# weaver_multisw.net
KiCad netlist of a schematic drawn in EAGLE
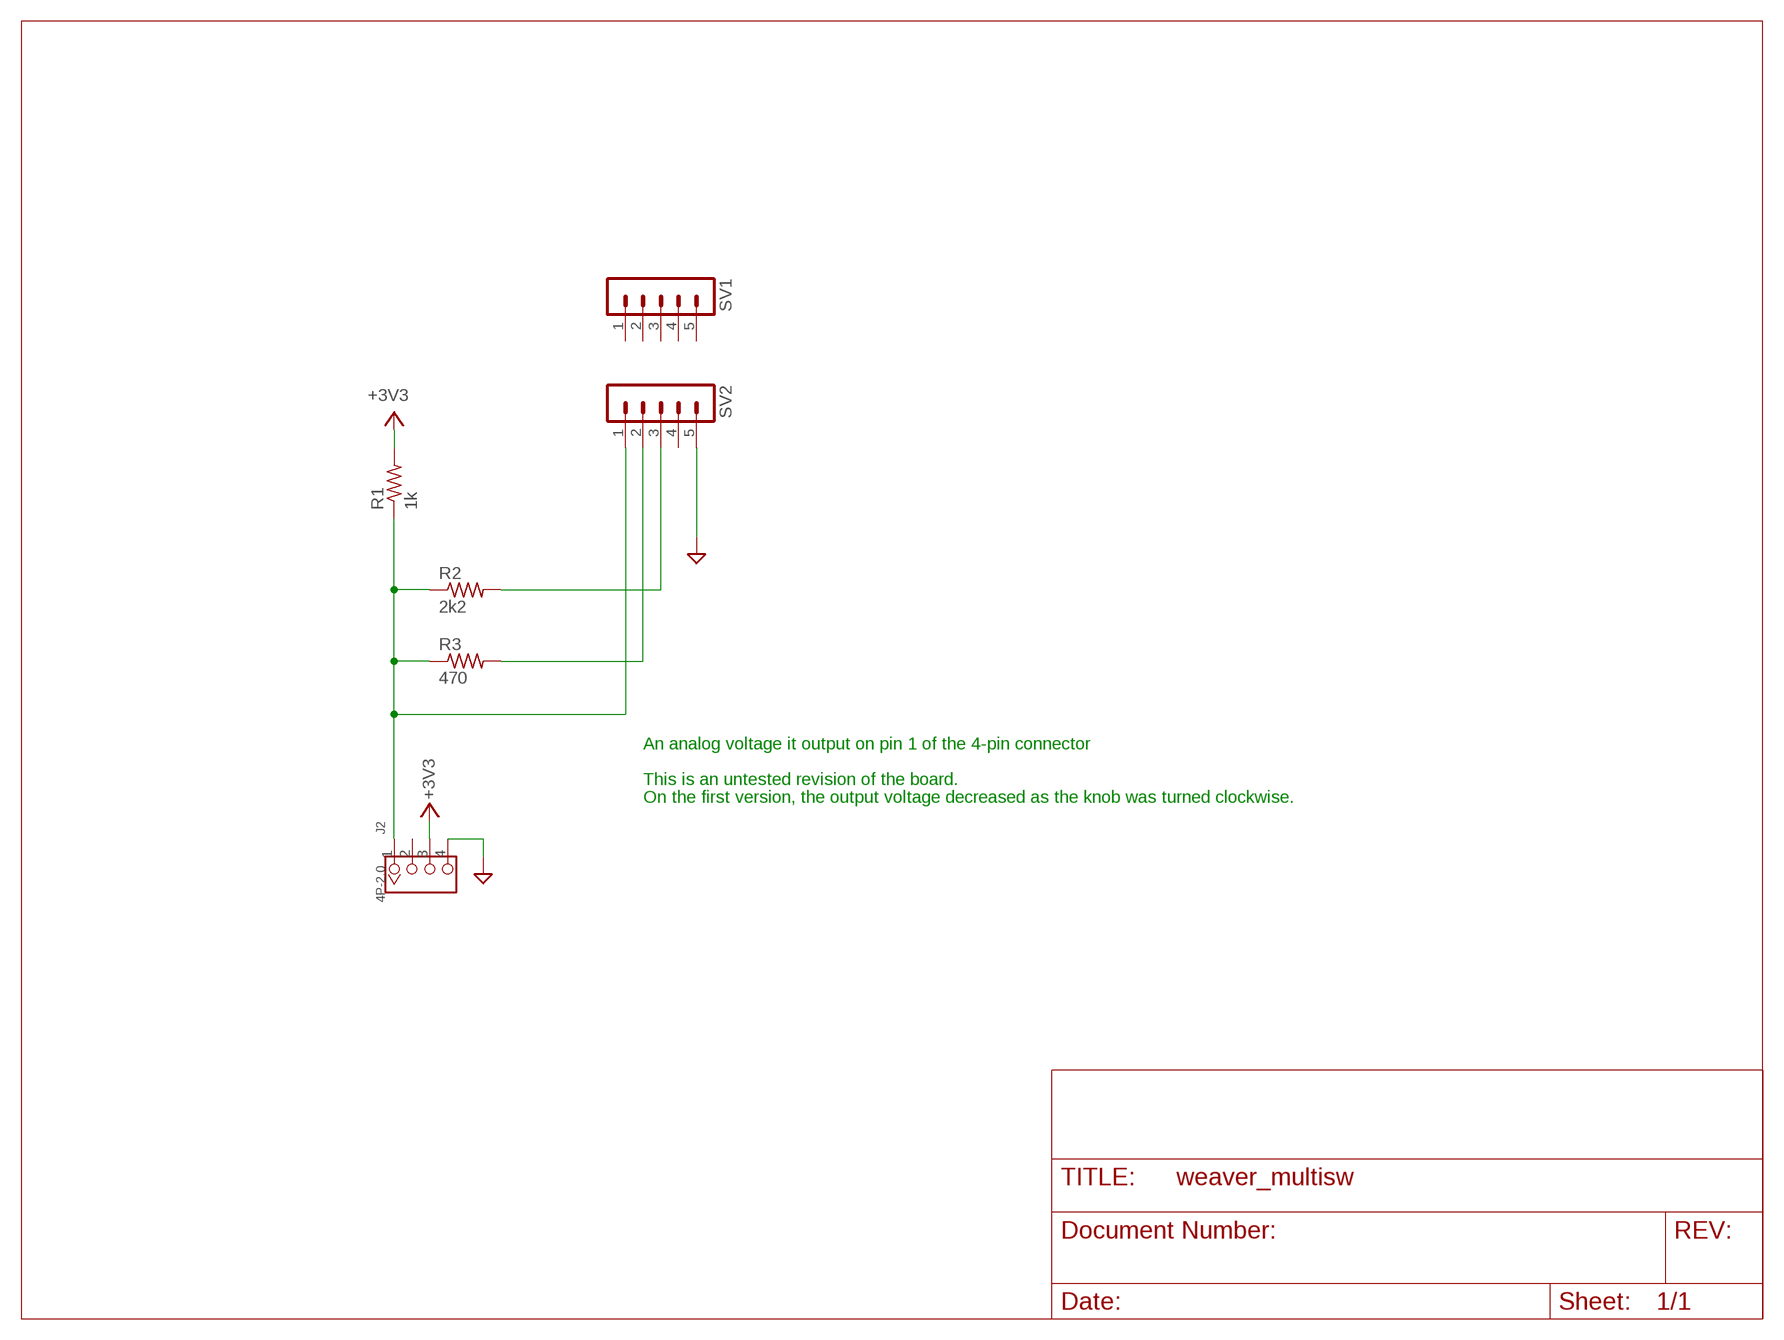
[diagram p0: schematic, sheet 1]

(export (version "E")
  (design (tool "Eeschema 10.0.6"))
  (components
    (comp (ref "J2")
      (value "4P-2.0")
      (footprint "eagle-import:HW4-2.0")
      (libsource (lib "eagle-import") (part "GROVE-CONNECTOR-DIP(4P-2.0)"))
    )
    (comp (ref "R1")
      (value "1k")
      (footprint "eagle-import:R0805")
      (libsource (lib "eagle-import") (part "R-US_R0805"))
    )
    (comp (ref "R2")
      (value "2k2")
      (footprint "eagle-import:R0805")
      (libsource (lib "eagle-import") (part "R-US_R0805"))
    )
    (comp (ref "R3")
      (value "470")
      (footprint "eagle-import:R0805")
      (libsource (lib "eagle-import") (part "R-US_R0805"))
    )
    (comp (ref "SV1")
      (value "MA05-1")
      (footprint "eagle-import:MA05-1")
      (libsource (lib "eagle-import") (part "MA05-1"))
    )
    (comp (ref "SV2")
      (value "MA05-1")
      (footprint "eagle-import:MA05-1")
      (libsource (lib "eagle-import") (part "MA05-1"))
    )
  )
  (nets
    (net (code "1") (name "+3V3") (class "Default")
      (node (ref "J2") (pin "3") (pinfunction "3_3") (pintype "bidirectional"))
      (node (ref "R1") (pin "2") (pinfunction "2_2") (pintype "passive"))
    )
    (net (code "2") (name "GND") (class "Default")
      (node (ref "J2") (pin "4") (pinfunction "4_4") (pintype "bidirectional"))
      (node (ref "SV2") (pin "5") (pinfunction "5_5") (pintype "passive"))
    )
    (net (code "3") (name "Net-(J2-Pad1)") (class "Default")
      (node (ref "J2") (pin "1") (pinfunction "1_1") (pintype "bidirectional"))
      (node (ref "R1") (pin "1") (pinfunction "1_1") (pintype "passive"))
      (node (ref "R2") (pin "1") (pinfunction "1_1") (pintype "passive"))
      (node (ref "R3") (pin "1") (pinfunction "1_1") (pintype "passive"))
      (node (ref "SV2") (pin "1") (pinfunction "1_1") (pintype "passive"))
    )
    (net (code "4") (name "Net-(R2-Pad2)") (class "Default")
      (node (ref "R2") (pin "2") (pinfunction "2_2") (pintype "passive"))
      (node (ref "SV2") (pin "3") (pinfunction "3_3") (pintype "passive"))
    )
    (net (code "5") (name "Net-(R3-Pad2)") (class "Default")
      (node (ref "R3") (pin "2") (pinfunction "2_2") (pintype "passive"))
      (node (ref "SV2") (pin "2") (pinfunction "2_2") (pintype "passive"))
    )
    (net (code "6") (name "unconnected-(J2-Pad2)") (class "Default")
      (node (ref "J2") (pin "2") (pinfunction "2_2") (pintype "bidirectional"))
    )
    (net (code "7") (name "unconnected-(SV1-Pad1)") (class "Default")
      (node (ref "SV1") (pin "1") (pinfunction "1_1") (pintype "passive"))
    )
    (net (code "8") (name "unconnected-(SV1-Pad2)") (class "Default")
      (node (ref "SV1") (pin "2") (pinfunction "2_2") (pintype "passive"))
    )
    (net (code "9") (name "unconnected-(SV1-Pad3)") (class "Default")
      (node (ref "SV1") (pin "3") (pinfunction "3_3") (pintype "passive"))
    )
    (net (code "10") (name "unconnected-(SV1-Pad4)") (class "Default")
      (node (ref "SV1") (pin "4") (pinfunction "4_4") (pintype "passive"))
    )
    (net (code "11") (name "unconnected-(SV1-Pad5)") (class "Default")
      (node (ref "SV1") (pin "5") (pinfunction "5_5") (pintype "passive"))
    )
    (net (code "12") (name "unconnected-(SV2-Pad4)") (class "Default")
      (node (ref "SV2") (pin "4") (pinfunction "4_4") (pintype "passive"))
    )
  )
)
